# PCB-2_0_v16.net
KiCad netlist of a schematic drawn in EAGLE
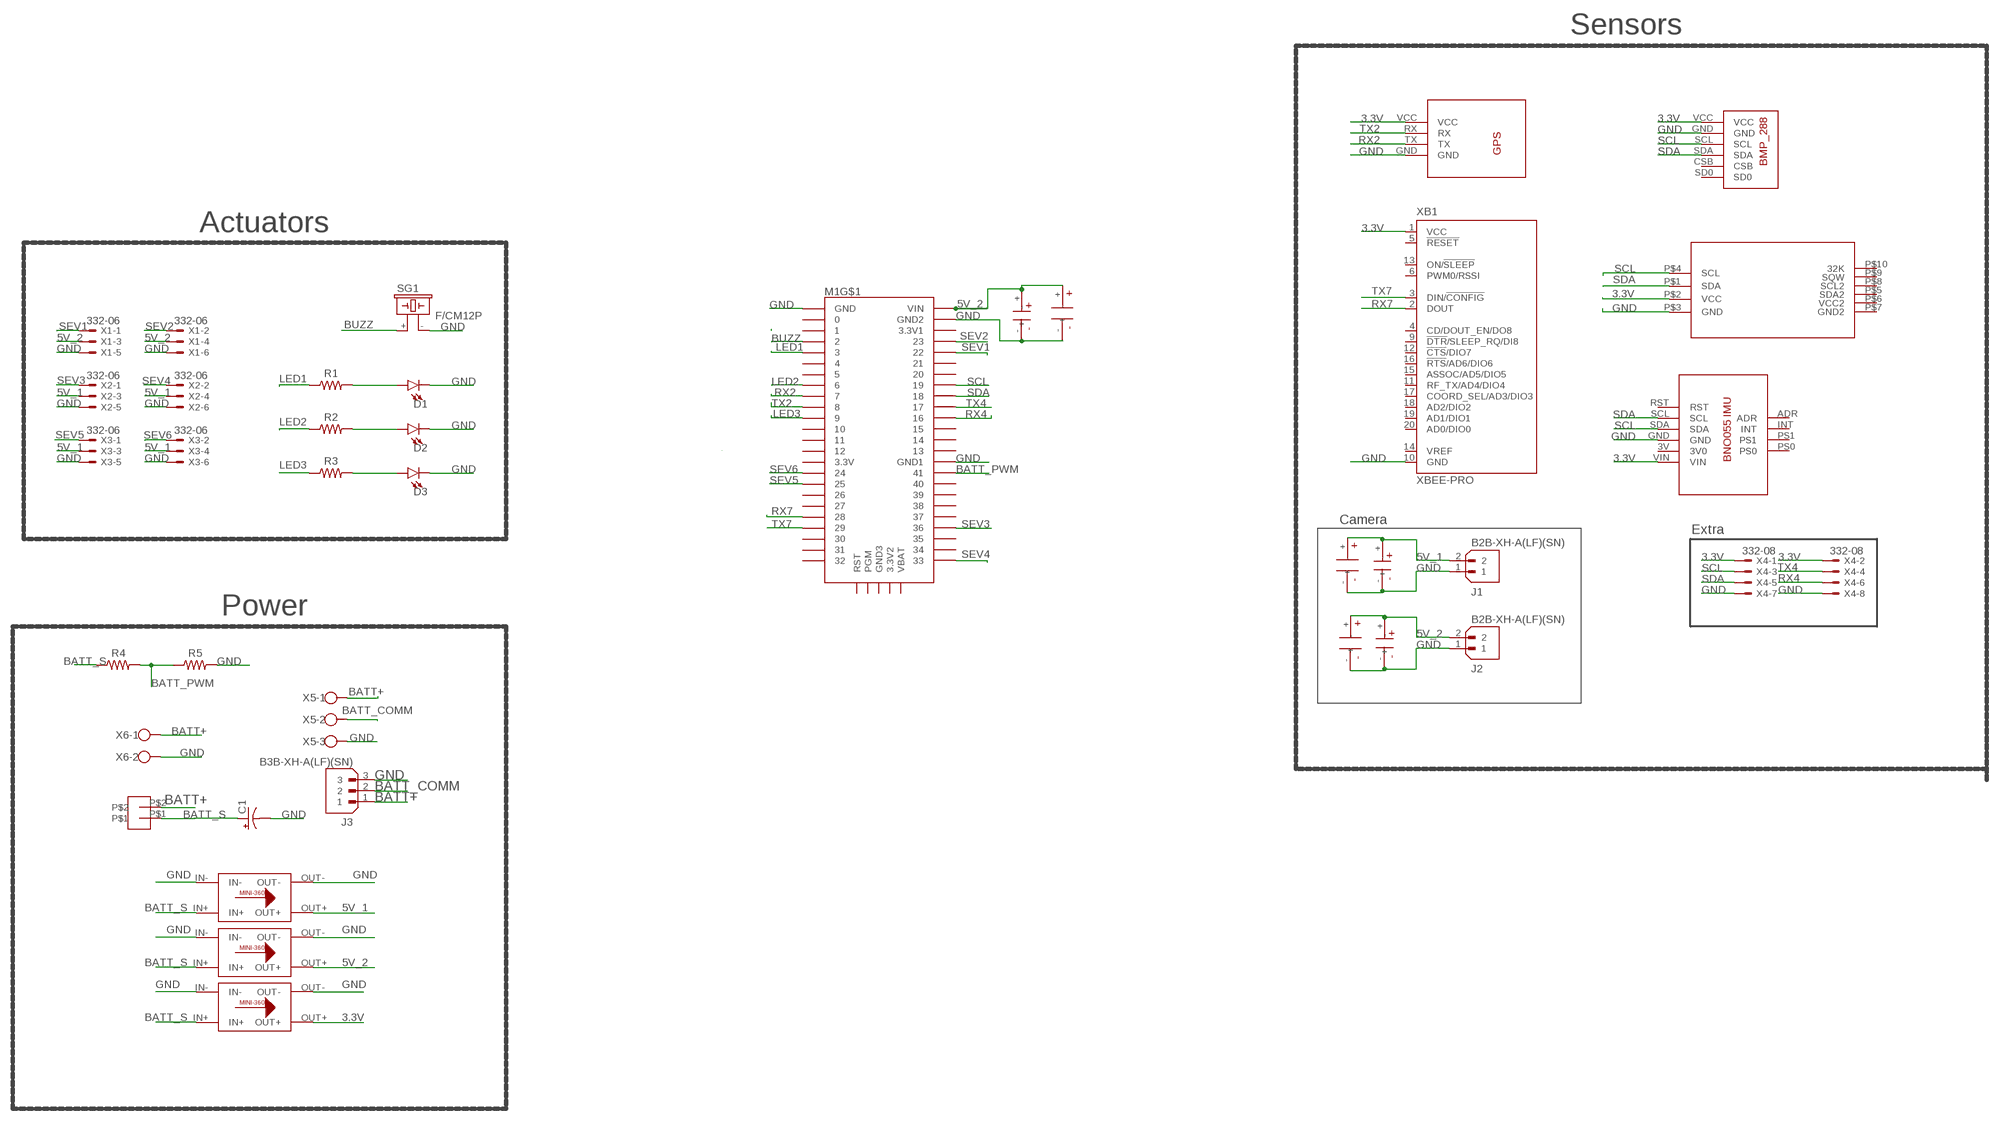
[diagram p0: schematic, sheet 1]

(export (version "E")
  (design (tool "Eeschema 10.0.6"))
  (components
    (comp (ref "C1")
      (value "1000UF-RADIAL-5MM-25V-20%-NO-SILK")
      (footprint "eagle-import:CPOL-RADIAL-5MM-10MM-NS")
      (libsource (lib "eagle-import") (part "1000UF-RADIAL-5MM-25V-20%-NO-SILK"))
    )
    (comp (ref "D1")
      (value "LED3MM")
      (footprint "eagle-import:LED_3MM")
      (libsource (lib "eagle-import") (part "LED3MM"))
    )
    (comp (ref "D2")
      (value "LED3MM")
      (footprint "eagle-import:LED_3MM")
      (libsource (lib "eagle-import") (part "LED3MM"))
    )
    (comp (ref "D3")
      (value "LED3MM")
      (footprint "eagle-import:LED_3MM")
      (libsource (lib "eagle-import") (part "LED3MM"))
    )
    (comp (ref "J1")
      (value "B2B-XH-A(LF)(SN)")
      (footprint "eagle-import:JST_B2B-XH-A(LF)(SN)")
      (fields (field (name "MF") "JST Sales"))
      (libsource (lib "eagle-import") (part "B2B-XH-A(LF)(SN)"))
    )
    (comp (ref "J2")
      (value "B2B-XH-A(LF)(SN)")
      (footprint "eagle-import:JST_B2B-XH-A(LF)(SN)")
      (fields (field (name "MF") "JST Sales"))
      (libsource (lib "eagle-import") (part "B2B-XH-A(LF)(SN)"))
    )
    (comp (ref "J3")
      (value "B3B-XH-A(LF)(SN)")
      (footprint "eagle-import:JST_B3B-XH-A(LF)(SN)")
      (fields (field (name "MF") "JST Sales"))
      (libsource (lib "eagle-import") (part "B3B-XH-A(LF)(SN)"))
    )
    (comp (ref "M1")
      (value "TEENSY4.1")
      (footprint "eagle-import:TEENSY4.1")
      (libsource (lib "eagle-import") (part "TEENSY4.1"))
    )
    (comp (ref "R1")
      (value "R-US_AXIAL-7.2MM-PITCH")
      (footprint "eagle-import:RESAD724W46L381D178B")
      (libsource (lib "eagle-import") (part "R-USAXIAL-7.2MM-PITCH_"))
    )
    (comp (ref "R2")
      (value "R-US_AXIAL-7.2MM-PITCH")
      (footprint "eagle-import:RESAD724W46L381D178B")
      (libsource (lib "eagle-import") (part "R-USAXIAL-7.2MM-PITCH_"))
    )
    (comp (ref "R3")
      (value "R-US_AXIAL-7.2MM-PITCH")
      (footprint "eagle-import:RESAD724W46L381D178B")
      (libsource (lib "eagle-import") (part "R-USAXIAL-7.2MM-PITCH_"))
    )
    (comp (ref "R4")
      (value "R-US_AXIAL-7.2MM-PITCH")
      (footprint "eagle-import:RESAD724W46L381D178B")
      (libsource (lib "eagle-import") (part "R-USAXIAL-7.2MM-PITCH_"))
    )
    (comp (ref "R5")
      (value "R-US_AXIAL-7.2MM-PITCH")
      (footprint "eagle-import:RESAD724W46L381D178B")
      (libsource (lib "eagle-import") (part "R-USAXIAL-7.2MM-PITCH_"))
    )
    (comp (ref "SG1")
      (value "F/CM12P")
      (footprint "eagle-import:F_CM12P")
      (libsource (lib "eagle-import") (part "F/CM12P"))
    )
    (comp (ref "U$1")
      (value "BMP_280THTOUGHHOLE")
      (footprint "eagle-import:BNO055_SELF")
      (libsource (lib "eagle-import") (part "BMP_280THTOUGHHOLE"))
    )
    (comp (ref "U$2")
      (value "GPS")
      (footprint "eagle-import:GPS")
      (libsource (lib "eagle-import") (part "GPS"))
    )
    (comp (ref "U$3")
      (value "VARY_BUCK")
      (footprint "eagle-import:VARY_BUCK")
      (libsource (lib "eagle-import") (part "VARY_BUCK"))
    )
    (comp (ref "U$4")
      (value "BNO055")
      (footprint "eagle-import:BNO055")
      (libsource (lib "eagle-import") (part "BNO055"))
    )
    (comp (ref "U$5")
      (value "VARY_BUCK")
      (footprint "eagle-import:VARY_BUCK")
      (libsource (lib "eagle-import") (part "VARY_BUCK"))
    )
    (comp (ref "U$6")
      (value "VARY_BUCK")
      (footprint "eagle-import:VARY_BUCK")
      (libsource (lib "eagle-import") (part "VARY_BUCK"))
    )
    (comp (ref "U$7")
      (value "DS3231_RTC")
      (footprint "eagle-import:DS3231_RTC")
      (libsource (lib "eagle-import") (part "DS3231_RTC"))
    )
    (comp (ref "U$9")
      (value "2_PIN")
      (footprint "eagle-import:2_PIN")
      (libsource (lib "eagle-import") (part "2_PIN"))
    )
    (comp (ref "U$10")
      (value "100UF-ELECTROLYTIC")
      (footprint "eagle-import:100UF_ELECTROLYTIC")
      (libsource (lib "eagle-import") (part "100UF-ELECTROLYTIC"))
    )
    (comp (ref "U$11")
      (value "100UF-ELECTROLYTIC")
      (footprint "eagle-import:100UF_ELECTROLYTIC")
      (libsource (lib "eagle-import") (part "100UF-ELECTROLYTIC"))
    )
    (comp (ref "U$12")
      (value "100UF-ELECTROLYTIC")
      (footprint "eagle-import:100UF_ELECTROLYTIC")
      (libsource (lib "eagle-import") (part "100UF-ELECTROLYTIC"))
    )
    (comp (ref "U$16")
      (value "0.1UF_CERAMIC")
      (footprint "eagle-import:0.1UF_CERAMIC")
      (libsource (lib "eagle-import") (part "0.1UF_CERAMIC"))
    )
    (comp (ref "U$17")
      (value "0.1UF_CERAMIC")
      (footprint "eagle-import:0.1UF_CERAMIC")
      (libsource (lib "eagle-import") (part "0.1UF_CERAMIC"))
    )
    (comp (ref "U$18")
      (value "0.1UF_CERAMIC")
      (footprint "eagle-import:0.1UF_CERAMIC")
      (libsource (lib "eagle-import") (part "0.1UF_CERAMIC"))
    )
    (comp (ref "X1")
      (value "332-06")
      (footprint "eagle-import:332-06")
      (libsource (lib "eagle-import") (part "332-06"))
    )
    (comp (ref "X2")
      (value "332-06")
      (footprint "eagle-import:332-06")
      (libsource (lib "eagle-import") (part "332-06"))
    )
    (comp (ref "X3")
      (value "332-06")
      (footprint "eagle-import:332-06")
      (libsource (lib "eagle-import") (part "332-06"))
    )
    (comp (ref "X4")
      (value "332-08")
      (footprint "eagle-import:332-08")
      (libsource (lib "eagle-import") (part "332-08"))
    )
    (comp (ref "X5")
      (value "W237-103")
      (footprint "eagle-import:W237-103")
      (fields (field (name "MPN") "237-103"))
      (libsource (lib "eagle-import") (part "W237-103"))
    )
    (comp (ref "X6")
      (value "W237-102")
      (footprint "eagle-import:W237-102")
      (fields (field (name "MPN") "237-102"))
      (libsource (lib "eagle-import") (part "W237-102"))
    )
    (comp (ref "XB1")
      (value "XBEE-PRO")
      (footprint "eagle-import:XBEE-PRO")
      (fields (field (name "MPN") "XBP24-AWI-001"))
      (libsource (lib "eagle-import") (part "XBEE-PRO"))
    )
  )
  (nets
    (net (code "1") (name "/3.3V") (class "Default")
      (node (ref "U$1") (pin "VCC") (pinfunction "VCC_VCC") (pintype "bidirectional"))
      (node (ref "U$2") (pin "VCC") (pinfunction "VCC_VCC") (pintype "bidirectional"))
      (node (ref "U$3") (pin "OUT+") (pinfunction "OUT+_OUT+") (pintype "bidirectional"))
      (node (ref "U$4") (pin "VIN") (pinfunction "VIN_VIN") (pintype "bidirectional"))
      (node (ref "U$7") (pin "P$2") (pinfunction "VCC_P$2") (pintype "bidirectional"))
      (node (ref "X4") (pin "1") (pinfunction "S_1") (pintype "passive"))
      (node (ref "X4") (pin "2") (pinfunction "S_2") (pintype "passive"))
      (node (ref "XB1") (pin "1") (pinfunction "VCC_1") (pintype "power_in"))
    )
    (net (code "2") (name "/5V_1") (class "Default")
      (node (ref "J1") (pin "2") (pinfunction "2_2") (pintype "passive"))
      (node (ref "U$10") (pin "+") (pinfunction "+_+") (pintype "bidirectional"))
      (node (ref "U$16") (pin "+") (pinfunction "+_+") (pintype "bidirectional"))
      (node (ref "U$5") (pin "OUT+") (pinfunction "OUT+_OUT+") (pintype "bidirectional"))
      (node (ref "X2") (pin "3") (pinfunction "S_3") (pintype "passive"))
      (node (ref "X2") (pin "4") (pinfunction "S_4") (pintype "passive"))
      (node (ref "X3") (pin "3") (pinfunction "S_3") (pintype "passive"))
      (node (ref "X3") (pin "4") (pinfunction "S_4") (pintype "passive"))
    )
    (net (code "3") (name "/5V_2") (class "Default")
      (node (ref "J2") (pin "2") (pinfunction "2_2") (pintype "passive"))
      (node (ref "M1") (pin "VIN") (pinfunction "VIN_VIN") (pintype "bidirectional"))
      (node (ref "U$11") (pin "+") (pinfunction "+_+") (pintype "bidirectional"))
      (node (ref "U$12") (pin "+") (pinfunction "+_+") (pintype "bidirectional"))
      (node (ref "U$17") (pin "+") (pinfunction "+_+") (pintype "bidirectional"))
      (node (ref "U$18") (pin "+") (pinfunction "+_+") (pintype "bidirectional"))
      (node (ref "U$6") (pin "OUT+") (pinfunction "OUT+_OUT+") (pintype "bidirectional"))
      (node (ref "X1") (pin "3") (pinfunction "S_3") (pintype "passive"))
      (node (ref "X1") (pin "4") (pinfunction "S_4") (pintype "passive"))
    )
    (net (code "4") (name "/BATT+") (class "Default")
      (node (ref "J3") (pin "1") (pinfunction "1_1") (pintype "passive"))
      (node (ref "U$9") (pin "P$2") (pinfunction "P$2_P$2") (pintype "bidirectional"))
      (node (ref "X5") (pin "1") (pinfunction "KL_1") (pintype "passive"))
      (node (ref "X6") (pin "1") (pinfunction "KL_1") (pintype "passive"))
    )
    (net (code "5") (name "/BATT_COMM") (class "Default")
      (node (ref "J3") (pin "2") (pinfunction "2_2") (pintype "passive"))
      (node (ref "X5") (pin "2") (pinfunction "KL_2") (pintype "passive"))
    )
    (net (code "6") (name "/BATT_PWM") (class "Default")
      (node (ref "M1") (pin "41") (pinfunction "41_41") (pintype "bidirectional"))
      (node (ref "R4") (pin "2") (pinfunction "2_2") (pintype "passive"))
      (node (ref "R5") (pin "1") (pinfunction "1_1") (pintype "passive"))
    )
    (net (code "7") (name "/BATT_S") (class "Default")
      (node (ref "C1") (pin "+") (pinfunction "+_+") (pintype "passive"))
      (node (ref "R4") (pin "1") (pinfunction "1_1") (pintype "passive"))
      (node (ref "U$3") (pin "IN+") (pinfunction "IN+_IN+") (pintype "bidirectional"))
      (node (ref "U$5") (pin "IN+") (pinfunction "IN+_IN+") (pintype "bidirectional"))
      (node (ref "U$6") (pin "IN+") (pinfunction "IN+_IN+") (pintype "bidirectional"))
      (node (ref "U$9") (pin "P$1") (pinfunction "P$1_P$1") (pintype "bidirectional"))
    )
    (net (code "8") (name "/BUZZ") (class "Default")
      (node (ref "M1") (pin "2") (pinfunction "2_2") (pintype "bidirectional"))
      (node (ref "SG1") (pin "+") (pinfunction "1_+") (pintype "passive"))
    )
    (net (code "9") (name "/GND") (class "Default")
      (node (ref "C1") (pin "-") (pinfunction "-_-") (pintype "passive"))
      (node (ref "D1") (pin "K") (pinfunction "C_K") (pintype "passive"))
      (node (ref "D2") (pin "K") (pinfunction "C_K") (pintype "passive"))
      (node (ref "D3") (pin "K") (pinfunction "C_K") (pintype "passive"))
      (node (ref "J1") (pin "1") (pinfunction "1_1") (pintype "passive"))
      (node (ref "J2") (pin "1") (pinfunction "1_1") (pintype "passive"))
      (node (ref "J3") (pin "3") (pinfunction "3_3") (pintype "passive"))
      (node (ref "M1") (pin "AGND") (pinfunction "GND2_AGND") (pintype "bidirectional"))
      (node (ref "M1") (pin "GND") (pinfunction "GND_GND") (pintype "bidirectional"))
      (node (ref "M1") (pin "GND1") (pinfunction "GND1_GND1") (pintype "bidirectional"))
      (node (ref "R5") (pin "2") (pinfunction "2_2") (pintype "passive"))
      (node (ref "SG1") (pin "-") (pinfunction "2_-") (pintype "passive"))
      (node (ref "U$1") (pin "GND") (pinfunction "GND_GND") (pintype "bidirectional"))
      (node (ref "U$10") (pin "-") (pinfunction "-_-") (pintype "bidirectional"))
      (node (ref "U$11") (pin "-") (pinfunction "-_-") (pintype "bidirectional"))
      (node (ref "U$12") (pin "-") (pinfunction "-_-") (pintype "bidirectional"))
      (node (ref "U$16") (pin "-") (pinfunction "-_-") (pintype "bidirectional"))
      (node (ref "U$17") (pin "-") (pinfunction "-_-") (pintype "bidirectional"))
      (node (ref "U$18") (pin "-") (pinfunction "-_-") (pintype "bidirectional"))
      (node (ref "U$2") (pin "GND") (pinfunction "GND_GND") (pintype "bidirectional"))
      (node (ref "U$3") (pin "IN-") (pinfunction "IN-_IN-") (pintype "bidirectional"))
      (node (ref "U$3") (pin "OUT-") (pinfunction "OUT-_OUT-") (pintype "bidirectional"))
      (node (ref "U$4") (pin "GND") (pinfunction "GND_GND") (pintype "bidirectional"))
      (node (ref "U$5") (pin "IN-") (pinfunction "IN-_IN-") (pintype "bidirectional"))
      (node (ref "U$5") (pin "OUT-") (pinfunction "OUT-_OUT-") (pintype "bidirectional"))
      (node (ref "U$6") (pin "IN-") (pinfunction "IN-_IN-") (pintype "bidirectional"))
      (node (ref "U$6") (pin "OUT-") (pinfunction "OUT-_OUT-") (pintype "bidirectional"))
      (node (ref "U$7") (pin "P$3") (pinfunction "GND_P$3") (pintype "bidirectional"))
      (node (ref "X1") (pin "5") (pinfunction "S_5") (pintype "passive"))
      (node (ref "X1") (pin "6") (pinfunction "S_6") (pintype "passive"))
      (node (ref "X2") (pin "5") (pinfunction "S_5") (pintype "passive"))
      (node (ref "X2") (pin "6") (pinfunction "S_6") (pintype "passive"))
      (node (ref "X3") (pin "5") (pinfunction "S_5") (pintype "passive"))
      (node (ref "X3") (pin "6") (pinfunction "S_6") (pintype "passive"))
      (node (ref "X4") (pin "7") (pinfunction "S_7") (pintype "passive"))
      (node (ref "X4") (pin "8") (pinfunction "S_8") (pintype "passive"))
      (node (ref "X5") (pin "3") (pinfunction "KL_3") (pintype "passive"))
      (node (ref "X6") (pin "2") (pinfunction "KL_2") (pintype "passive"))
      (node (ref "XB1") (pin "10") (pinfunction "GND_10") (pintype "power_in"))
    )
    (net (code "10") (name "/LED1") (class "Default")
      (node (ref "M1") (pin "3") (pinfunction "3_3") (pintype "bidirectional"))
      (node (ref "R1") (pin "1") (pinfunction "1_1") (pintype "passive"))
    )
    (net (code "11") (name "/LED2") (class "Default")
      (node (ref "M1") (pin "6") (pinfunction "6_6") (pintype "bidirectional"))
      (node (ref "R2") (pin "1") (pinfunction "1_1") (pintype "passive"))
    )
    (net (code "12") (name "/LED3") (class "Default")
      (node (ref "M1") (pin "9") (pinfunction "9_9") (pintype "bidirectional"))
      (node (ref "R3") (pin "1") (pinfunction "1_1") (pintype "passive"))
    )
    (net (code "13") (name "/RX2") (class "Default")
      (node (ref "M1") (pin "7") (pinfunction "7_7") (pintype "bidirectional"))
      (node (ref "U$2") (pin "TX") (pinfunction "TX_TX") (pintype "bidirectional"))
    )
    (net (code "14") (name "/RX4") (class "Default")
      (node (ref "M1") (pin "16/A2") (pinfunction "16_16/A2") (pintype "bidirectional"))
      (node (ref "X4") (pin "6") (pinfunction "S_6") (pintype "passive"))
    )
    (net (code "15") (name "/RX7") (class "Default")
      (node (ref "M1") (pin "28") (pinfunction "28_28") (pintype "bidirectional"))
      (node (ref "XB1") (pin "2") (pinfunction "DOUT_2") (pintype "output"))
    )
    (net (code "16") (name "/SCL") (class "Default")
      (node (ref "M1") (pin "19/A5/SCL") (pinfunction "19_19/A5/SCL") (pintype "bidirectional"))
      (node (ref "U$1") (pin "SCL") (pinfunction "SCL_SCL") (pintype "bidirectional"))
      (node (ref "U$4") (pin "SDA") (pinfunction "SDA_SDA") (pintype "bidirectional"))
      (node (ref "U$7") (pin "P$4") (pinfunction "SCL_P$4") (pintype "bidirectional"))
      (node (ref "X4") (pin "3") (pinfunction "S_3") (pintype "passive"))
    )
    (net (code "17") (name "/SDA") (class "Default")
      (node (ref "M1") (pin "18/A4/SDA") (pinfunction "18_18/A4/SDA") (pintype "bidirectional"))
      (node (ref "U$1") (pin "SDA") (pinfunction "SDA_SDA") (pintype "bidirectional"))
      (node (ref "U$4") (pin "SCL") (pinfunction "SCL_SCL") (pintype "bidirectional"))
      (node (ref "U$7") (pin "P$1") (pinfunction "SDA_P$1") (pintype "bidirectional"))
      (node (ref "X4") (pin "5") (pinfunction "S_5") (pintype "passive"))
    )
    (net (code "18") (name "/SEV1") (class "Default")
      (node (ref "M1") (pin "22/A8") (pinfunction "22_22/A8") (pintype "bidirectional"))
      (node (ref "X1") (pin "1") (pinfunction "S_1") (pintype "passive"))
    )
    (net (code "19") (name "/SEV2") (class "Default")
      (node (ref "M1") (pin "23/A9") (pinfunction "23_23/A9") (pintype "bidirectional"))
      (node (ref "X1") (pin "2") (pinfunction "S_2") (pintype "passive"))
    )
    (net (code "20") (name "/SEV3") (class "Default")
      (node (ref "M1") (pin "36") (pinfunction "36_36") (pintype "bidirectional"))
      (node (ref "X2") (pin "1") (pinfunction "S_1") (pintype "passive"))
    )
    (net (code "21") (name "/SEV4") (class "Default")
      (node (ref "M1") (pin "33") (pinfunction "33_33") (pintype "bidirectional"))
      (node (ref "X2") (pin "2") (pinfunction "S_2") (pintype "passive"))
    )
    (net (code "22") (name "/SEV5") (class "Default")
      (node (ref "M1") (pin "25") (pinfunction "25_25") (pintype "bidirectional"))
      (node (ref "X3") (pin "1") (pinfunction "S_1") (pintype "passive"))
    )
    (net (code "23") (name "/SEV6") (class "Default")
      (node (ref "M1") (pin "24") (pinfunction "24_24") (pintype "bidirectional"))
      (node (ref "X3") (pin "2") (pinfunction "S_2") (pintype "passive"))
    )
    (net (code "24") (name "/TX2") (class "Default")
      (node (ref "M1") (pin "8") (pinfunction "8_8") (pintype "bidirectional"))
      (node (ref "U$2") (pin "RX") (pinfunction "RX_RX") (pintype "bidirectional"))
    )
    (net (code "25") (name "/TX4") (class "Default")
      (node (ref "M1") (pin "17/A3") (pinfunction "17_17/A3") (pintype "bidirectional"))
      (node (ref "X4") (pin "4") (pinfunction "S_4") (pintype "passive"))
    )
    (net (code "26") (name "/TX7") (class "Default")
      (node (ref "M1") (pin "29") (pinfunction "29_29") (pintype "bidirectional"))
      (node (ref "XB1") (pin "3") (pinfunction "DIN/~{CONFIG}_3") (pintype "input"))
    )
    (net (code "27") (name "Net-(D1-PadA)") (class "Default")
      (node (ref "D1") (pin "A") (pinfunction "A_A") (pintype "passive"))
      (node (ref "R1") (pin "2") (pinfunction "2_2") (pintype "passive"))
    )
    (net (code "28") (name "Net-(D2-PadA)") (class "Default")
      (node (ref "D2") (pin "A") (pinfunction "A_A") (pintype "passive"))
      (node (ref "R2") (pin "2") (pinfunction "2_2") (pintype "passive"))
    )
    (net (code "29") (name "Net-(D3-PadA)") (class "Default")
      (node (ref "D3") (pin "A") (pinfunction "A_A") (pintype "passive"))
      (node (ref "R3") (pin "2") (pinfunction "2_2") (pintype "passive"))
    )
    (net (code "30") (name "unconnected-(M1-Pad4)") (class "Default")
      (node (ref "M1") (pin "4") (pinfunction "4_4") (pintype "bidirectional"))
    )
    (net (code "31") (name "unconnected-(M1-Pad5)") (class "Default")
      (node (ref "M1") (pin "5") (pinfunction "5_5") (pintype "bidirectional"))
    )
    (net (code "32") (name "unconnected-(M1-Pad26)") (class "Default")
      (node (ref "M1") (pin "26") (pinfunction "26_26") (pintype "bidirectional"))
    )
    (net (code "33") (name "unconnected-(M1-Pad27)") (class "Default")
      (node (ref "M1") (pin "27") (pinfunction "27_27") (pintype "bidirectional"))
    )
    (net (code "34") (name "unconnected-(M1-Pad30)") (class "Default")
      (node (ref "M1") (pin "30") (pinfunction "30_30") (pintype "bidirectional"))
    )
    (net (code "35") (name "unconnected-(M1-Pad32)") (class "Default")
      (node (ref "M1") (pin "32") (pinfunction "32_32") (pintype "bidirectional"))
    )
    (net (code "36") (name "unconnected-(M1-Pad34)") (class "Default")
      (node (ref "M1") (pin "34") (pinfunction "34_34") (pintype "bidirectional"))
    )
    (net (code "37") (name "unconnected-(M1-Pad35)") (class "Default")
      (node (ref "M1") (pin "35") (pinfunction "35_35") (pintype "bidirectional"))
    )
    (net (code "38") (name "unconnected-(M1-Pad37)") (class "Default")
      (node (ref "M1") (pin "37") (pinfunction "37_37") (pintype "bidirectional"))
    )
    (net (code "39") (name "unconnected-(M1-Pad38)") (class "Default")
      (node (ref "M1") (pin "38") (pinfunction "38_38") (pintype "bidirectional"))
    )
    (net (code "40") (name "unconnected-(M1-Pad39)") (class "Default")
      (node (ref "M1") (pin "39") (pinfunction "39_39") (pintype "bidirectional"))
    )
    (net (code "41") (name "unconnected-(M1-Pad40)") (class "Default")
      (node (ref "M1") (pin "40") (pinfunction "40_40") (pintype "bidirectional"))
    )
    (net (code "42") (name "unconnected-(M1-PadRST)") (class "Default")
      (node (ref "M1") (pin "RST") (pinfunction "RST_RST") (pintype "bidirectional"))
    )
    (net (code "43") (name "unconnected-(M1-PadVBAT)") (class "Default")
      (node (ref "M1") (pin "VBAT") (pinfunction "VBAT_VBAT") (pintype "bidirectional"))
    )
    (net (code "44") (name "unconnected-(M1A-0-Pad0{slash}RX)") (class "Default")
      (node (ref "M1") (pin "0/RX") (pinfunction "0_0/RX") (pintype "bidirectional"))
    )
    (net (code "45") (name "unconnected-(M1A-1-Pad1{slash}TX)") (class "Default")
      (node (ref "M1") (pin "1/TX") (pinfunction "1_1/TX") (pintype "bidirectional"))
    )
    (net (code "46") (name "unconnected-(M1A-3.3V-Pad3V3)") (class "Default")
      (node (ref "M1") (pin "3V3") (pinfunction "3.3V_3V3") (pintype "bidirectional"))
    )
    (net (code "47") (name "unconnected-(M1A-3.3V1-Pad3V3_LO)") (class "Default")
      (node (ref "M1") (pin "3V3_LO") (pinfunction "3.3V1_3V3_LO") (pintype "bidirectional"))
    )
    (net (code "48") (name "unconnected-(M1A-3.3V2-PadV33)") (class "Default")
      (node (ref "M1") (pin "V33") (pinfunction "3.3V2_V33") (pintype "bidirectional"))
    )
    (net (code "49") (name "unconnected-(M1A-10-Pad10{slash}CS)") (class "Default")
      (node (ref "M1") (pin "10/CS") (pinfunction "10_10/CS") (pintype "bidirectional"))
    )
    (net (code "50") (name "unconnected-(M1A-11-Pad11{slash}MOSI)") (class "Default")
      (node (ref "M1") (pin "11/MOSI") (pinfunction "11_11/MOSI") (pintype "bidirectional"))
    )
    (net (code "51") (name "unconnected-(M1A-12-Pad12{slash}MISO)") (class "Default")
      (node (ref "M1") (pin "12/MISO") (pinfunction "12_12/MISO") (pintype "bidirectional"))
    )
    (net (code "52") (name "unconnected-(M1A-13-Pad13{slash}SCK)") (class "Default")
      (node (ref "M1") (pin "13/SCK") (pinfunction "13_13/SCK") (pintype "bidirectional"))
    )
    (net (code "53") (name "unconnected-(M1A-14-Pad14{slash}A0)") (class "Default")
      (node (ref "M1") (pin "14/A0") (pinfunction "14_14/A0") (pintype "bidirectional"))
    )
    (net (code "54") (name "unconnected-(M1A-15-Pad15{slash}A1)") (class "Default")
      (node (ref "M1") (pin "15/A1") (pinfunction "15_15/A1") (pintype "bidirectional"))
    )
    (net (code "55") (name "unconnected-(M1A-20-Pad20{slash}A6)") (class "Default")
      (node (ref "M1") (pin "20/A6") (pinfunction "20_20/A6") (pintype "bidirectional"))
    )
    (net (code "56") (name "unconnected-(M1A-21-Pad21{slash}A7)") (class "Default")
      (node (ref "M1") (pin "21/A7") (pinfunction "21_21/A7") (pintype "bidirectional"))
    )
    (net (code "57") (name "unconnected-(M1A-31-Pad31{slash}A12)") (class "Default")
      (node (ref "M1") (pin "31/A12") (pinfunction "31_31/A12") (pintype "bidirectional"))
    )
    (net (code "58") (name "unconnected-(M1A-GND3-PadGND2)") (class "Default")
      (node (ref "M1") (pin "GND2") (pinfunction "GND3_GND2") (pintype "bidirectional"))
    )
    (net (code "59") (name "unconnected-(M1A-PGM-PadPROG)") (class "Default")
      (node (ref "M1") (pin "PROG") (pinfunction "PGM_PROG") (pintype "bidirectional"))
    )
    (net (code "60") (name "unconnected-(U$1-PadCSB)") (class "Default")
      (node (ref "U$1") (pin "CSB") (pinfunction "CSB_CSB") (pintype "bidirectional"))
    )
    (net (code "61") (name "unconnected-(U$1-PadSD0)") (class "Default")
      (node (ref "U$1") (pin "SD0") (pinfunction "SD0_SD0") (pintype "bidirectional"))
    )
    (net (code "62") (name "unconnected-(U$4-3V0-Pad3V)") (class "Default")
      (node (ref "U$4") (pin "3V") (pinfunction "3V0_3V") (pintype "bidirectional"))
    )
    (net (code "63") (name "unconnected-(U$4-PadADR)") (class "Default")
      (node (ref "U$4") (pin "ADR") (pinfunction "ADR_ADR") (pintype "bidirectional"))
    )
    (net (code "64") (name "unconnected-(U$4-PadINT)") (class "Default")
      (node (ref "U$4") (pin "INT") (pinfunction "INT_INT") (pintype "bidirectional"))
    )
    (net (code "65") (name "unconnected-(U$4-PadPS0)") (class "Default")
      (node (ref "U$4") (pin "PS0") (pinfunction "PS0_PS0") (pintype "bidirectional"))
    )
    (net (code "66") (name "unconnected-(U$4-PadPS1)") (class "Default")
      (node (ref "U$4") (pin "PS1") (pinfunction "PS1_PS1") (pintype "bidirectional"))
    )
    (net (code "67") (name "unconnected-(U$4-PadRST)") (class "Default")
      (node (ref "U$4") (pin "RST") (pinfunction "RST_RST") (pintype "bidirectional"))
    )
    (net (code "68") (name "unconnected-(U$7-32K-PadP$10)") (class "Default")
      (node (ref "U$7") (pin "P$10") (pinfunction "32K_P$10") (pintype "bidirectional"))
    )
    (net (code "69") (name "unconnected-(U$7-GND2-PadP$7)") (class "Default")
      (node (ref "U$7") (pin "P$7") (pinfunction "GND2_P$7") (pintype "bidirectional"))
    )
    (net (code "70") (name "unconnected-(U$7-SCL2-PadP$8)") (class "Default")
      (node (ref "U$7") (pin "P$8") (pinfunction "SCL2_P$8") (pintype "bidirectional"))
    )
    (net (code "71") (name "unconnected-(U$7-SDA2-PadP$5)") (class "Default")
      (node (ref "U$7") (pin "P$5") (pinfunction "SDA2_P$5") (pintype "bidirectional"))
    )
    (net (code "72") (name "unconnected-(U$7-SQW-PadP$9)") (class "Default")
      (node (ref "U$7") (pin "P$9") (pinfunction "SQW_P$9") (pintype "bidirectional"))
    )
    (net (code "73") (name "unconnected-(U$7-VCC2-PadP$6)") (class "Default")
      (node (ref "U$7") (pin "P$6") (pinfunction "VCC2_P$6") (pintype "bidirectional"))
    )
    (net (code "74") (name "unconnected-(XB1-AD0{slash}DIO0-Pad20)") (class "Default")
      (node (ref "XB1") (pin "20") (pinfunction "AD0/DIO0_20") (pintype "bidirectional"))
    )
    (net (code "75") (name "unconnected-(XB1-AD1{slash}DIO1-Pad19)") (class "Default")
      (node (ref "XB1") (pin "19") (pinfunction "AD1/DIO1_19") (pintype "bidirectional"))
    )
    (net (code "76") (name "unconnected-(XB1-AD2{slash}DIO2-Pad18)") (class "Default")
      (node (ref "XB1") (pin "18") (pinfunction "AD2/DIO2_18") (pintype "bidirectional"))
    )
    (net (code "77") (name "unconnected-(XB1-ASSOC{slash}AD5{slash}DIO5-Pad15)") (class "Default")
      (node (ref "XB1") (pin "15") (pinfunction "ASSOC/AD5/DIO5_15") (pintype "bidirectional"))
    )
    (net (code "78") (name "unconnected-(XB1-CD{slash}DOUT_EN{slash}DO8-Pad4)") (class "Default")
      (node (ref "XB1") (pin "4") (pinfunction "CD/DOUT_EN/DO8_4") (pintype "output"))
    )
    (net (code "79") (name "unconnected-(XB1-COORD_SEL{slash}AD3{slash}DIO3-Pad17)") (class "Default")
      (node (ref "XB1") (pin "17") (pinfunction "COORD_SEL/AD3/DIO3_17") (pintype "bidirectional"))
    )
    (net (code "80") (name "unconnected-(XB1-ON{slash}~{SLEEP}-Pad13)") (class "Default")
      (node (ref "XB1") (pin "13") (pinfunction "ON/~{SLEEP}_13") (pintype "output"))
    )
    (net (code "81") (name "unconnected-(XB1-PWM0{slash}RSSI-Pad6)") (class "Default")
      (node (ref "XB1") (pin "6") (pinfunction "PWM0/RSSI_6") (pintype "output"))
    )
    (net (code "82") (name "unconnected-(XB1-RF_TX{slash}AD4{slash}DIO4-Pad11)") (class "Default")
      (node (ref "XB1") (pin "11") (pinfunction "RF_TX/AD4/DIO4_11") (pintype "bidirectional"))
    )
    (net (code "83") (name "unconnected-(XB1-VREF-Pad14)") (class "Default")
      (node (ref "XB1") (pin "14") (pinfunction "VREF_14") (pintype "input"))
    )
    (net (code "84") (name "unconnected-(XB1-~{CTS}{slash}DIO7-Pad12)") (class "Default")
      (node (ref "XB1") (pin "12") (pinfunction "~{CTS}/DIO7_12") (pintype "bidirectional"))
    )
    (net (code "85") (name "unconnected-(XB1-~{DTR}{slash}SLEEP_RQ{slash}DI8-Pad9)") (class "Default")
      (node (ref "XB1") (pin "9") (pinfunction "~{DTR}/SLEEP_RQ/DI8_9") (pintype "bidirectional"))
    )
    (net (code "86") (name "unconnected-(XB1-~{RESET}-Pad5)") (class "Default")
      (node (ref "XB1") (pin "5") (pinfunction "~{RESET}_5") (pintype "input"))
    )
    (net (code "87") (name "unconnected-(XB1-~{RTS}{slash}AD6{slash}DIO6-Pad16)") (class "Default")
      (node (ref "XB1") (pin "16") (pinfunction "~{RTS}/AD6/DIO6_16") (pintype "bidirectional"))
    )
  )
)
